# powerBoard-2nd.net
KiCad netlist of a schematic drawn in EAGLE
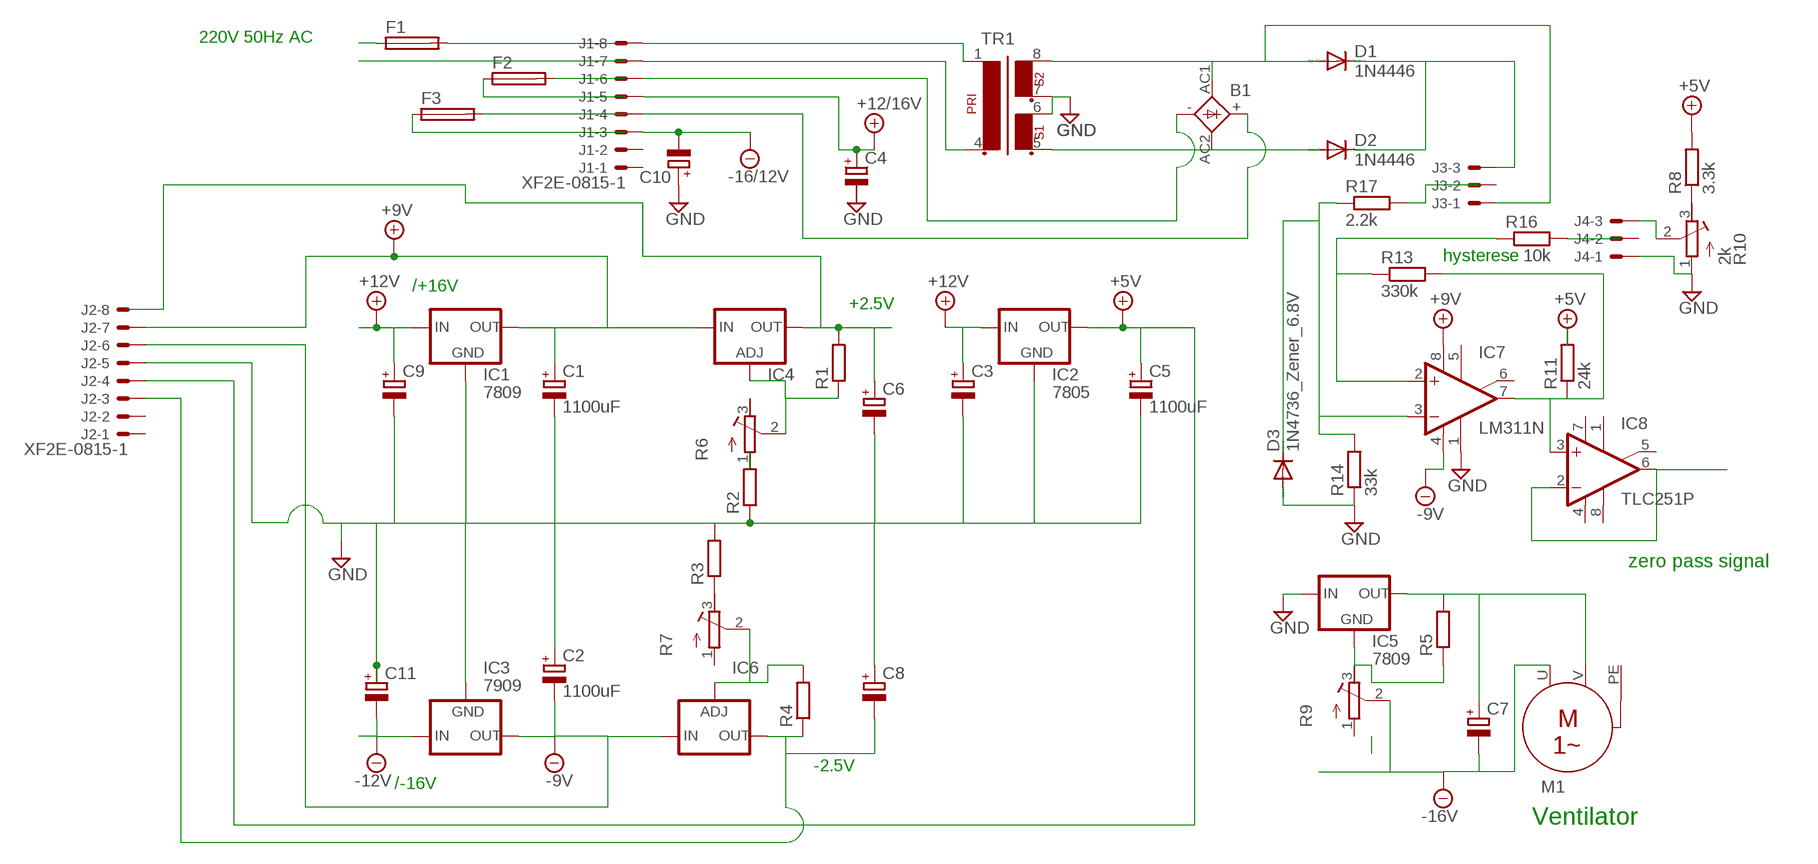
[diagram p0: schematic, sheet 1]

(export (version "E")
  (design (tool "Eeschema 10.0.6"))
  (components
    (comp (ref "B1")
      (value "DSI32A")
      (footprint "eagle-import:DSI32A")
      (libsource (lib "eagle-import") (part "DSI32A"))
    )
    (comp (ref "C1")
      (value "1100uF")
      (footprint "eagle-import:E22-6")
      (libsource (lib "eagle-import") (part "CPOL-EUE22-6AXIAL"))
    )
    (comp (ref "C2")
      (value "1100uF")
      (footprint "eagle-import:E22-6")
      (libsource (lib "eagle-import") (part "CPOL-EUE22-6AXIAL"))
    )
    (comp (ref "C3")
      (value "CPOL-EUE22-6AXIAL")
      (footprint "eagle-import:E22-6")
      (libsource (lib "eagle-import") (part "CPOL-EUE22-6AXIAL"))
    )
    (comp (ref "C4")
      (value "CPOL-EUE22-6AXIAL")
      (footprint "eagle-import:E22-6")
      (libsource (lib "eagle-import") (part "CPOL-EUE22-6AXIAL"))
    )
    (comp (ref "C5")
      (value "1100uF")
      (footprint "eagle-import:E22-6")
      (libsource (lib "eagle-import") (part "CPOL-EUE22-6AXIAL"))
    )
    (comp (ref "C6")
      (value "CPOL-EUE22-6AXIAL")
      (footprint "eagle-import:E22-6")
      (libsource (lib "eagle-import") (part "CPOL-EUE22-6AXIAL"))
    )
    (comp (ref "C7")
      (value "CPOL-EUE22-6AXIAL")
      (footprint "eagle-import:E22-6")
      (libsource (lib "eagle-import") (part "CPOL-EUE22-6AXIAL"))
    )
    (comp (ref "C8")
      (value "CPOL-EUE22-6AXIAL")
      (footprint "eagle-import:E22-6")
      (libsource (lib "eagle-import") (part "CPOL-EUE22-6AXIAL"))
    )
    (comp (ref "C9")
      (value "CPOL-EUE22-6AXIAL")
      (footprint "eagle-import:E22-6")
      (libsource (lib "eagle-import") (part "CPOL-EUE22-6AXIAL"))
    )
    (comp (ref "C10")
      (value "CPOL-EUE22-6AXIAL")
      (footprint "eagle-import:E22-6")
      (libsource (lib "eagle-import") (part "CPOL-EUE22-6AXIAL"))
    )
    (comp (ref "C11")
      (value "CPOL-EUE22-6AXIAL")
      (footprint "eagle-import:E22-6")
      (libsource (lib "eagle-import") (part "CPOL-EUE22-6AXIAL"))
    )
    (comp (ref "D1")
      (value "1N4446")
      (footprint "eagle-import:DO35-10")
      (libsource (lib "eagle-import") (part "1N4446"))
    )
    (comp (ref "D2")
      (value "1N4446")
      (footprint "eagle-import:DO35-10")
      (libsource (lib "eagle-import") (part "1N4446"))
    )
    (comp (ref "D3")
      (value "1N4736_Zener_6.8V")
      (footprint "eagle-import:DO35-10")
      (libsource (lib "eagle-import") (part "1N4446"))
    )
    (comp (ref "F1")
      (value "SH25")
      (footprint "eagle-import:SH25")
      (libsource (lib "eagle-import") (part "SH25"))
    )
    (comp (ref "F2")
      (value "SH25")
      (footprint "eagle-import:SH25")
      (libsource (lib "eagle-import") (part "SH25"))
    )
    (comp (ref "F3")
      (value "SH25")
      (footprint "eagle-import:SH25")
      (libsource (lib "eagle-import") (part "SH25"))
    )
    (comp (ref "IC1")
      (value "7809")
      (footprint "eagle-import:78LXX")
      (libsource (lib "eagle-import") (part "78LXX"))
    )
    (comp (ref "IC2")
      (value "7805")
      (footprint "eagle-import:78LXX")
      (libsource (lib "eagle-import") (part "78LXX"))
    )
    (comp (ref "IC3")
      (value "7909")
      (footprint "eagle-import:79LXX")
      (libsource (lib "eagle-import") (part "79LXX"))
    )
    (comp (ref "IC4")
      (value "LM317-T039")
      (footprint "eagle-import:TO39-H03")
      (libsource (lib "eagle-import") (part "LM317-T039"))
    )
    (comp (ref "IC5")
      (value "7809")
      (footprint "eagle-import:78LXX")
      (libsource (lib "eagle-import") (part "78LXX"))
    )
    (comp (ref "IC6")
      (value "LM337-TO3")
      (footprint "eagle-import:TO3-K02")
      (libsource (lib "eagle-import") (part "LM337-TO3"))
    )
    (comp (ref "IC7")
      (value "LM311N")
      (footprint "eagle-import:DIL08")
      (libsource (lib "eagle-import") (part "LM311N"))
    )
    (comp (ref "IC8")
      (value "TLC251P")
      (footprint "eagle-import:DIL08")
      (libsource (lib "eagle-import") (part "TLC251P"))
    )
    (comp (ref "J1")
      (value "XF2E-0815-1")
      (footprint "eagle-import:XF2E-0815-1")
      (libsource (lib "eagle-import") (part "XF2-08?15-1E"))
    )
    (comp (ref "J2")
      (value "XF2E-0815-1")
      (footprint "eagle-import:XF2E-0815-1")
      (libsource (lib "eagle-import") (part "XF2-08?15-1E"))
    )
    (comp (ref "J3")
      (value "XF2E-0815-1")
      (footprint "eagle-import:XF2E-0815-1")
      (libsource (lib "eagle-import") (part "XF2-08?15-1E"))
    )
    (comp (ref "J4")
      (value "XF2E-0815-1")
      (footprint "eagle-import:XF2E-0815-1")
      (libsource (lib "eagle-import") (part "XF2-08?15-1E"))
    )
    (comp (ref "M1")
      (value "MOTOR_1-PHASEN")
      (footprint "eagle-import:MOTOR_1-PHASEN")
      (libsource (lib "eagle-import") (part "MOTOR_1-PHASEN"))
    )
    (comp (ref "R1")
      (value "R-EU_0309/V")
      (footprint "eagle-import:0309V")
      (libsource (lib "eagle-import") (part "R-EU_0309/V"))
    )
    (comp (ref "R2")
      (value "R-EU_0309/V")
      (footprint "eagle-import:0309V")
      (libsource (lib "eagle-import") (part "R-EU_0309/V"))
    )
    (comp (ref "R3")
      (value "R-EU_0309/V")
      (footprint "eagle-import:0309V")
      (libsource (lib "eagle-import") (part "R-EU_0309/V"))
    )
    (comp (ref "R4")
      (value "R-EU_0309/V")
      (footprint "eagle-import:0309V")
      (libsource (lib "eagle-import") (part "R-EU_0309/V"))
    )
    (comp (ref "R5")
      (value "R-EU_0309/V")
      (footprint "eagle-import:0309V")
      (libsource (lib "eagle-import") (part "R-EU_0309/V"))
    )
    (comp (ref "R6")
      (value "R-TRIMM4G/J")
      (footprint "eagle-import:RTRIM4G_J")
      (libsource (lib "eagle-import") (part "R-TRIMM4G/J"))
    )
    (comp (ref "R7")
      (value "R-TRIMM4G/J")
      (footprint "eagle-import:RTRIM4G_J")
      (libsource (lib "eagle-import") (part "R-TRIMM4G/J"))
    )
    (comp (ref "R8")
      (value "3.3k")
      (footprint "eagle-import:0309V")
      (libsource (lib "eagle-import") (part "R-EU_0309/V"))
    )
    (comp (ref "R9")
      (value "R-TRIMM4G/J")
      (footprint "eagle-import:RTRIM4G_J")
      (libsource (lib "eagle-import") (part "R-TRIMM4G/J"))
    )
    (comp (ref "R10")
      (value "2k")
      (footprint "eagle-import:RTRIM4G_J")
      (libsource (lib "eagle-import") (part "R-TRIMM4G/J"))
    )
    (comp (ref "R11")
      (value "24k")
      (footprint "eagle-import:0309V")
      (libsource (lib "eagle-import") (part "R-EU_0309/V"))
    )
    (comp (ref "R13")
      (value "330k")
      (footprint "eagle-import:0309V")
      (libsource (lib "eagle-import") (part "R-EU_0309/V"))
    )
    (comp (ref "R14")
      (value "33k")
      (footprint "eagle-import:0309V")
      (libsource (lib "eagle-import") (part "R-EU_0309/V"))
    )
    (comp (ref "R16")
      (value "10k")
      (footprint "eagle-import:0309V")
      (libsource (lib "eagle-import") (part "R-EU_0309/V"))
    )
    (comp (ref "R17")
      (value "2.2k")
      (footprint "eagle-import:0309V")
      (libsource (lib "eagle-import") (part "R-EU_0309/V"))
    )
    (comp (ref "TR1")
      (value "EE20-2")
      (footprint "eagle-import:EE20-2")
      (libsource (lib "eagle-import") (part "EE20-2"))
    )
  )
  (nets
    (net (code "1") (name "+5V") (class "Default")
      (node (ref "C5") (pin "+") (pinfunction "+_+") (pintype "passive"))
      (node (ref "IC2") (pin "OUT") (pinfunction "OUT_OUT") (pintype "passive"))
      (node (ref "J2") (pin "4") (pinfunction "MS_4") (pintype "passive"))
      (node (ref "R11") (pin "2") (pinfunction "2_2") (pintype "passive"))
      (node (ref "R8") (pin "2") (pinfunction "2_2") (pintype "passive"))
    )
    (net (code "2") (name "+9V") (class "Default")
      (node (ref "C1") (pin "+") (pinfunction "+_+") (pintype "passive"))
      (node (ref "IC1") (pin "OUT") (pinfunction "OUT_OUT") (pintype "passive"))
      (node (ref "IC4") (pin "1") (pinfunction "IN_1") (pintype "input"))
      (node (ref "IC7") (pin "8") (pinfunction "V+_8") (pintype "power_in"))
      (node (ref "J2") (pin "7") (pinfunction "MS_7") (pintype "passive"))
    )
    (net (code "3") (name "+12V") (class "Default")
      (node (ref "C3") (pin "+") (pinfunction "+_+") (pintype "passive"))
      (node (ref "C4") (pin "+") (pinfunction "+_+") (pintype "passive"))
      (node (ref "C9") (pin "+") (pinfunction "+_+") (pintype "passive"))
      (node (ref "IC1") (pin "IN") (pinfunction "IN_IN") (pintype "input"))
      (node (ref "IC2") (pin "IN") (pinfunction "IN_IN") (pintype "input"))
      (node (ref "J1") (pin "5") (pinfunction "MS_5") (pintype "passive"))
    )
    (net (code "4") (name "-9V") (class "Default")
      (node (ref "C2") (pin "-") (pinfunction "-_-") (pintype "passive"))
      (node (ref "IC3") (pin "OUT") (pinfunction "OUT_OUT") (pintype "passive"))
      (node (ref "IC6") (pin "3") (pinfunction "IN_3") (pintype "input"))
      (node (ref "IC7") (pin "4") (pinfunction "V-_4") (pintype "power_in"))
      (node (ref "J2") (pin "6") (pinfunction "MS_6") (pintype "passive"))
    )
    (net (code "5") (name "-12V") (class "Default")
      (node (ref "C10") (pin "-") (pinfunction "-_-") (pintype "passive"))
      (node (ref "C11") (pin "-") (pinfunction "-_-") (pintype "passive"))
      (node (ref "C7") (pin "-") (pinfunction "-_-") (pintype "passive"))
      (node (ref "IC3") (pin "IN") (pinfunction "IN_IN") (pintype "input"))
      (node (ref "J1") (pin "3") (pinfunction "MS_3") (pintype "passive"))
      (node (ref "M1") (pin "U") (pinfunction "U_U") (pintype "passive"))
      (node (ref "R9") (pin "2") (pinfunction "S_2") (pintype "passive"))
    )
    (net (code "6") (name "/V+") (class "Default")
      (node (ref "IC8") (pin "7") (pinfunction "V+_7") (pintype "power_in"))
    )
    (net (code "7") (name "/V-") (class "Default")
      (node (ref "IC8") (pin "4") (pinfunction "V-_4") (pintype "power_in"))
    )
    (net (code "8") (name "GND") (class "Default")
      (node (ref "C1") (pin "-") (pinfunction "-_-") (pintype "passive"))
      (node (ref "C10") (pin "+") (pinfunction "+_+") (pintype "passive"))
      (node (ref "C11") (pin "+") (pinfunction "+_+") (pintype "passive"))
      (node (ref "C2") (pin "+") (pinfunction "+_+") (pintype "passive"))
      (node (ref "C3") (pin "-") (pinfunction "-_-") (pintype "passive"))
      (node (ref "C5") (pin "-") (pinfunction "-_-") (pintype "passive"))
      (node (ref "C6") (pin "-") (pinfunction "-_-") (pintype "passive"))
      (node (ref "C8") (pin "+") (pinfunction "+_+") (pintype "passive"))
      (node (ref "C9") (pin "-") (pinfunction "-_-") (pintype "passive"))
      (node (ref "D3") (pin "A") (pinfunction "A_A") (pintype "passive"))
      (node (ref "IC1") (pin "GND") (pinfunction "GND_GND") (pintype "input"))
      (node (ref "IC2") (pin "GND") (pinfunction "GND_GND") (pintype "input"))
      (node (ref "IC3") (pin "GND") (pinfunction "GND_GND") (pintype "input"))
      (node (ref "IC5") (pin "IN") (pinfunction "IN_IN") (pintype "input"))
      (node (ref "IC7") (pin "1") (pinfunction "GND_1") (pintype "passive"))
      (node (ref "J2") (pin "5") (pinfunction "MS_5") (pintype "passive"))
      (node (ref "J4") (pin "1") (pinfunction "MSV_1") (pintype "passive"))
      (node (ref "R10") (pin "1") (pinfunction "A_1") (pintype "passive"))
      (node (ref "R14") (pin "1") (pinfunction "1_1") (pintype "passive"))
      (node (ref "R2") (pin "1") (pinfunction "1_1") (pintype "passive"))
      (node (ref "R3") (pin "2") (pinfunction "2_2") (pintype "passive"))
      (node (ref "TR1") (pin "6") (pinfunction "4_6") (pintype "passive"))
      (node (ref "TR1") (pin "7") (pinfunction "5_7") (pintype "passive"))
    )
    (net (code "9") (name "Net-(C7-Pad+)") (class "Default")
      (node (ref "C7") (pin "+") (pinfunction "+_+") (pintype "passive"))
      (node (ref "IC5") (pin "OUT") (pinfunction "OUT_OUT") (pintype "passive"))
      (node (ref "M1") (pin "V") (pinfunction "V_V") (pintype "passive"))
      (node (ref "R5") (pin "2") (pinfunction "2_2") (pintype "passive"))
    )
    (net (code "10") (name "Net-(IC4-ADJ)") (class "Default")
      (node (ref "IC4") (pin "2") (pinfunction "ADJ_2") (pintype "input"))
      (node (ref "R1") (pin "1") (pinfunction "1_1") (pintype "passive"))
      (node (ref "R6") (pin "2") (pinfunction "S_2") (pintype "passive"))
    )
    (net (code "11") (name "Net-(IC4-OUT)") (class "Default")
      (node (ref "C6") (pin "+") (pinfunction "+_+") (pintype "passive"))
      (node (ref "IC4") (pin "3") (pinfunction "OUT_3") (pintype "passive"))
      (node (ref "J2") (pin "8") (pinfunction "MS_8") (pintype "passive"))
      (node (ref "R1") (pin "2") (pinfunction "2_2") (pintype "passive"))
    )
    (net (code "12") (name "Net-(IC6-ADJ)") (class "Default")
      (node (ref "IC6") (pin "2") (pinfunction "ADJ_2") (pintype "input"))
      (node (ref "R4") (pin "2") (pinfunction "2_2") (pintype "passive"))
      (node (ref "R7") (pin "2") (pinfunction "S_2") (pintype "passive"))
    )
    (net (code "13") (name "Net-(IC6-OUT)") (class "Default")
      (node (ref "C8") (pin "-") (pinfunction "-_-") (pintype "passive"))
      (node (ref "IC6") (pin "1") (pinfunction "OUT_1") (pintype "passive"))
      (node (ref "J2") (pin "3") (pinfunction "MS_3") (pintype "passive"))
      (node (ref "R4") (pin "1") (pinfunction "1_1") (pintype "passive"))
    )
    (net (code "14") (name "Net-(IC7-+IN)") (class "Default")
      (node (ref "IC7") (pin "2") (pinfunction "+IN_2") (pintype "input"))
      (node (ref "R13") (pin "1") (pinfunction "1_1") (pintype "passive"))
      (node (ref "R16") (pin "1") (pinfunction "1_1") (pintype "passive"))
    )
    (net (code "15") (name "Net-(IC7--IN)") (class "Default")
      (node (ref "D3") (pin "C") (pinfunction "C_C") (pintype "passive"))
      (node (ref "IC7") (pin "3") (pinfunction "-IN_3") (pintype "input"))
      (node (ref "R14") (pin "2") (pinfunction "2_2") (pintype "passive"))
      (node (ref "R17") (pin "1") (pinfunction "1_1") (pintype "passive"))
    )
    (net (code "16") (name "Net-(IC7-OUT)") (class "Default")
      (node (ref "IC7") (pin "7") (pinfunction "OUT_7") (pintype "output"))
      (node (ref "IC8") (pin "3") (pinfunction "+IN_3") (pintype "input"))
      (node (ref "R11") (pin "1") (pinfunction "1_1") (pintype "passive"))
      (node (ref "R13") (pin "2") (pinfunction "2_2") (pintype "passive"))
    )
    (net (code "17") (name "Net-(IC8--IN)") (class "Default")
      (node (ref "IC8") (pin "2") (pinfunction "-IN_2") (pintype "input"))
      (node (ref "IC8") (pin "6") (pinfunction "OUT_6") (pintype "output"))
    )
    (net (code "18") (name "Net-(J1D-MS)") (class "Default")
      (node (ref "B1") (pin "+") (pinfunction "+_+") (pintype "passive"))
      (node (ref "J1") (pin "4") (pinfunction "MS_4") (pintype "passive"))
    )
    (net (code "19") (name "Net-(J1F-MS)") (class "Default")
      (node (ref "B1") (pin "-") (pinfunction "-_-") (pintype "passive"))
      (node (ref "J1") (pin "6") (pinfunction "MS_6") (pintype "passive"))
    )
    (net (code "20") (name "Net-(J1G-MS)") (class "Default")
      (node (ref "J1") (pin "7") (pinfunction "MS_7") (pintype "passive"))
      (node (ref "TR1") (pin "4") (pinfunction "2_4") (pintype "passive"))
    )
    (net (code "21") (name "Net-(J1H-MS)") (class "Default")
      (node (ref "J1") (pin "8") (pinfunction "MS_8") (pintype "passive"))
      (node (ref "TR1") (pin "1") (pinfunction "1_1") (pintype "passive"))
    )
    (net (code "22") (name "Net-(J3A-MSV)") (class "Default")
      (node (ref "B1") (pin "AC1") (pinfunction "AC1_AC1") (pintype "passive"))
      (node (ref "D1") (pin "A") (pinfunction "A_A") (pintype "passive"))
      (node (ref "J3") (pin "1") (pinfunction "MSV_1") (pintype "passive"))
      (node (ref "TR1") (pin "8") (pinfunction "6_8") (pintype "passive"))
    )
    (net (code "23") (name "Net-(J3C-MS)") (class "Default")
      (node (ref "D1") (pin "C") (pinfunction "C_C") (pintype "passive"))
      (node (ref "D2") (pin "C") (pinfunction "C_C") (pintype "passive"))
      (node (ref "J3") (pin "3") (pinfunction "MS_3") (pintype "passive"))
    )
    (net (code "24") (name "Net-(J4C-MS)") (class "Default")
      (node (ref "J4") (pin "3") (pinfunction "MS_3") (pintype "passive"))
      (node (ref "R10") (pin "2") (pinfunction "S_2") (pintype "passive"))
    )
    (net (code "25") (name "Net-(R6-A)") (class "Default")
      (node (ref "R2") (pin "2") (pinfunction "2_2") (pintype "passive"))
      (node (ref "R6") (pin "1") (pinfunction "A_1") (pintype "passive"))
    )
    (net (code "26") (name "Net-(R7-E)") (class "Default")
      (node (ref "R3") (pin "1") (pinfunction "1_1") (pintype "passive"))
      (node (ref "R7") (pin "3") (pinfunction "E_3") (pintype "passive"))
    )
    (net (code "27") (name "Net-(R9-E)") (class "Default")
      (node (ref "IC5") (pin "GND") (pinfunction "GND_GND") (pintype "input"))
      (node (ref "R5") (pin "1") (pinfunction "1_1") (pintype "passive"))
      (node (ref "R9") (pin "3") (pinfunction "E_3") (pintype "passive"))
    )
    (net (code "28") (name "Net-(R10-E)") (class "Default")
      (node (ref "R10") (pin "3") (pinfunction "E_3") (pintype "passive"))
      (node (ref "R8") (pin "1") (pinfunction "1_1") (pintype "passive"))
    )
    (net (code "29") (name "Net-(TR1-3)") (class "Default")
      (node (ref "B1") (pin "AC2") (pinfunction "AC2_AC2") (pintype "passive"))
      (node (ref "TR1") (pin "5") (pinfunction "3_5") (pintype "passive"))
    )
    (net (code "30") (name "unconnected-(C4-Pad-)") (class "Default")
      (node (ref "C4") (pin "-") (pinfunction "-_-") (pintype "passive"))
    )
    (net (code "31") (name "unconnected-(D2-PadA)") (class "Default")
      (node (ref "D2") (pin "A") (pinfunction "A_A") (pintype "passive"))
    )
    (net (code "32") (name "unconnected-(F1-Pad1)") (class "Default")
      (node (ref "F1") (pin "1") (pinfunction "1_1") (pintype "passive"))
    )
    (net (code "33") (name "unconnected-(F1-Pad2)") (class "Default")
      (node (ref "F1") (pin "2") (pinfunction "2_2") (pintype "passive"))
    )
    (net (code "34") (name "unconnected-(F2-Pad1)") (class "Default")
      (node (ref "F2") (pin "1") (pinfunction "1_1") (pintype "passive"))
    )
    (net (code "35") (name "unconnected-(F2-Pad2)") (class "Default")
      (node (ref "F2") (pin "2") (pinfunction "2_2") (pintype "passive"))
    )
    (net (code "36") (name "unconnected-(F3-Pad1)") (class "Default")
      (node (ref "F3") (pin "1") (pinfunction "1_1") (pintype "passive"))
    )
    (net (code "37") (name "unconnected-(F3-Pad2)") (class "Default")
      (node (ref "F3") (pin "2") (pinfunction "2_2") (pintype "passive"))
    )
    (net (code "38") (name "unconnected-(IC7-ON-Pad5)") (class "Default")
      (node (ref "IC7") (pin "5") (pinfunction "ON_5") (pintype "passive"))
    )
    (net (code "39") (name "unconnected-(IC7-ON{slash}STR-Pad6)") (class "Default")
      (node (ref "IC7") (pin "6") (pinfunction "ON/STR_6") (pintype "passive"))
    )
    (net (code "40") (name "unconnected-(IC8-ON1-Pad1)") (class "Default")
      (node (ref "IC8") (pin "1") (pinfunction "ON1_1") (pintype "passive"))
    )
    (net (code "41") (name "unconnected-(IC8-ON2-Pad5)") (class "Default")
      (node (ref "IC8") (pin "5") (pinfunction "ON2_5") (pintype "passive"))
    )
    (net (code "42") (name "unconnected-(IC8-OPT-Pad8)") (class "Default")
      (node (ref "IC8") (pin "8") (pinfunction "OPT_8") (pintype "passive"))
    )
    (net (code "43") (name "unconnected-(J1A-MSV-Pad1)") (class "Default")
      (node (ref "J1") (pin "1") (pinfunction "MSV_1") (pintype "passive"))
    )
    (net (code "44") (name "unconnected-(J1B-MS-Pad2)") (class "Default")
      (node (ref "J1") (pin "2") (pinfunction "MS_2") (pintype "passive"))
    )
    (net (code "45") (name "unconnected-(J2A-MSV-Pad1)") (class "Default")
      (node (ref "J2") (pin "1") (pinfunction "MSV_1") (pintype "passive"))
    )
    (net (code "46") (name "unconnected-(J2B-MS-Pad2)") (class "Default")
      (node (ref "J2") (pin "2") (pinfunction "MS_2") (pintype "passive"))
    )
    (net (code "47") (name "unconnected-(J3B-MS-Pad2)") (class "Default")
      (node (ref "J3") (pin "2") (pinfunction "MS_2") (pintype "passive"))
    )
    (net (code "48") (name "unconnected-(J4B-MS-Pad2)") (class "Default")
      (node (ref "J4") (pin "2") (pinfunction "MS_2") (pintype "passive"))
    )
    (net (code "49") (name "unconnected-(M1-PadPE)") (class "Default")
      (node (ref "M1") (pin "PE") (pinfunction "PE_PE") (pintype "passive"))
    )
    (net (code "50") (name "unconnected-(R6-E-Pad3)") (class "Default")
      (node (ref "R6") (pin "3") (pinfunction "E_3") (pintype "passive"))
    )
    (net (code "51") (name "unconnected-(R7-A-Pad1)") (class "Default")
      (node (ref "R7") (pin "1") (pinfunction "A_1") (pintype "passive"))
    )
    (net (code "52") (name "unconnected-(R9-A-Pad1)") (class "Default")
      (node (ref "R9") (pin "1") (pinfunction "A_1") (pintype "passive"))
    )
    (net (code "53") (name "unconnected-(R16-Pad2)") (class "Default")
      (node (ref "R16") (pin "2") (pinfunction "2_2") (pintype "passive"))
    )
    (net (code "54") (name "unconnected-(R17-Pad2)") (class "Default")
      (node (ref "R17") (pin "2") (pinfunction "2_2") (pintype "passive"))
    )
  )
)
